# Laboratoire3_ClavierI2C.net
KiCad netlist of a schematic drawn in Altium Designer
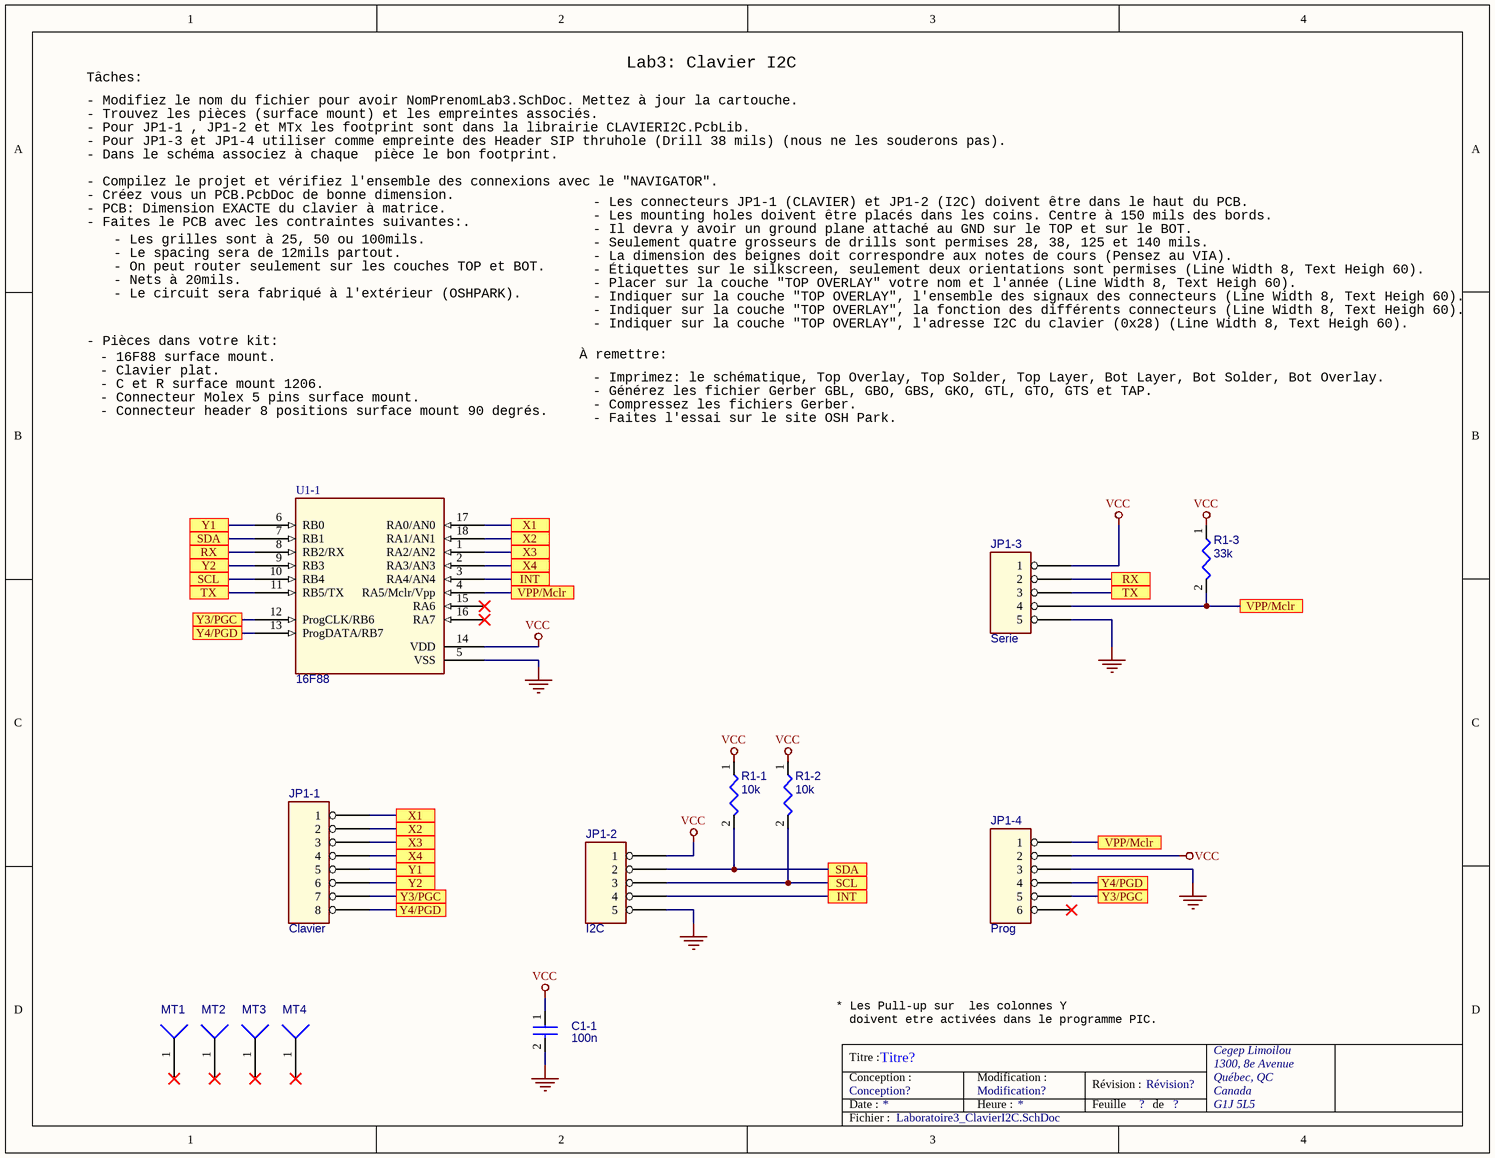
[diagram p0: Laboratoire3_ClavierI2C.SchDoc]

(export (version "E")
  (design (tool "Eeschema 10.0.6"))
  (components
    (comp (ref "C1-1") (value "100n") (libsource (lib "*") (part "CAP NP")))
    (comp (ref "JP1-1") (value "Clavier") (libsource (lib "*") (part "HEADER 8")))
    (comp (ref "JP1-2") (value "I2C") (libsource (lib "*") (part "HEADER 5")))
    (comp (ref "JP1-3") (value "Serie") (libsource (lib "*") (part "HEADER 5")))
    (comp (ref "JP1-4") (value "Prog") (libsource (lib "*") (part "HEADER 6")))
    (comp (ref "MT1") (value "MT") (libsource (lib "*") (part "CONNECTOR COAX-F")))
    (comp (ref "MT2") (value "MT") (libsource (lib "*") (part "CONNECTOR COAX-F")))
    (comp (ref "MT3") (value "MT") (libsource (lib "*") (part "CONNECTOR COAX-F")))
    (comp (ref "MT4") (value "MT") (libsource (lib "*") (part "CONNECTOR COAX-F")))
    (comp (ref "R1-1") (value "10k") (libsource (lib "*") (part "R")))
    (comp (ref "R1-2") (value "10k") (libsource (lib "*") (part "R")))
    (comp (ref "R1-3") (value "33k") (libsource (lib "*") (part "R")))
    (comp (ref "U1-1") (value "16F88") (libsource (lib "CLAVIERI2C") (part "16F88")))
  )
  (nets
    (net (code "1") (name "/INT") (class "Default")
      (node (ref "JP1-2") (pin "4") (pinfunction "4_4") (pintype "passive"))
      (node (ref "U1-1") (pin "3") (pinfunction "RA4/AN4_3") (pintype "input"))
    )
    (net (code "2") (name "/RX") (class "Default")
      (node (ref "JP1-3") (pin "2") (pinfunction "2_2") (pintype "passive"))
      (node (ref "U1-1") (pin "8") (pinfunction "RB2/RX_8") (pintype "input"))
    )
    (net (code "3") (name "/SCL") (class "Default")
      (node (ref "JP1-2") (pin "3") (pinfunction "3_3") (pintype "passive"))
      (node (ref "R1-2") (pin "2") (pinfunction "2_2") (pintype "passive"))
      (node (ref "U1-1") (pin "10") (pinfunction "RB4_10") (pintype "input"))
    )
    (net (code "4") (name "/SDA") (class "Default")
      (node (ref "JP1-2") (pin "2") (pinfunction "2_2") (pintype "passive"))
      (node (ref "R1-1") (pin "2") (pinfunction "2_2") (pintype "passive"))
      (node (ref "U1-1") (pin "7") (pinfunction "RB1_7") (pintype "input"))
    )
    (net (code "5") (name "/TX") (class "Default")
      (node (ref "JP1-3") (pin "3") (pinfunction "3_3") (pintype "passive"))
      (node (ref "U1-1") (pin "11") (pinfunction "RB5/TX_11") (pintype "input"))
    )
    (net (code "6") (name "/VPP{slash}Mclr") (class "Default")
      (node (ref "JP1-3") (pin "4") (pinfunction "4_4") (pintype "passive"))
      (node (ref "JP1-4") (pin "1") (pinfunction "1_1") (pintype "passive"))
      (node (ref "R1-3") (pin "2") (pinfunction "2_2") (pintype "passive"))
      (node (ref "U1-1") (pin "4") (pinfunction "RA5/Mclr/Vpp_4") (pintype "input"))
    )
    (net (code "7") (name "/X1") (class "Default")
      (node (ref "JP1-1") (pin "1") (pinfunction "1_1") (pintype "passive"))
      (node (ref "U1-1") (pin "17") (pinfunction "RA0/AN0_17") (pintype "input"))
    )
    (net (code "8") (name "/X2") (class "Default")
      (node (ref "JP1-1") (pin "2") (pinfunction "2_2") (pintype "passive"))
      (node (ref "U1-1") (pin "18") (pinfunction "RA1/AN1_18") (pintype "input"))
    )
    (net (code "9") (name "/X3") (class "Default")
      (node (ref "JP1-1") (pin "3") (pinfunction "3_3") (pintype "passive"))
      (node (ref "U1-1") (pin "1") (pinfunction "RA2/AN2_1") (pintype "input"))
    )
    (net (code "10") (name "/X4") (class "Default")
      (node (ref "JP1-1") (pin "4") (pinfunction "4_4") (pintype "passive"))
      (node (ref "U1-1") (pin "2") (pinfunction "RA3/AN3_2") (pintype "input"))
    )
    (net (code "11") (name "/Y1") (class "Default")
      (node (ref "JP1-1") (pin "5") (pinfunction "5_5") (pintype "passive"))
      (node (ref "U1-1") (pin "6") (pinfunction "RB0_6") (pintype "input"))
    )
    (net (code "12") (name "/Y2") (class "Default")
      (node (ref "JP1-1") (pin "6") (pinfunction "6_6") (pintype "passive"))
      (node (ref "U1-1") (pin "9") (pinfunction "RB3_9") (pintype "input"))
    )
    (net (code "13") (name "/Y3{slash}PGC") (class "Default")
      (node (ref "JP1-1") (pin "7") (pinfunction "7_7") (pintype "passive"))
      (node (ref "JP1-4") (pin "5") (pinfunction "5_5") (pintype "passive"))
      (node (ref "U1-1") (pin "12") (pinfunction "ProgCLK/RB6_12") (pintype "input"))
    )
    (net (code "14") (name "/Y4{slash}PGD") (class "Default")
      (node (ref "JP1-1") (pin "8") (pinfunction "8_8") (pintype "passive"))
      (node (ref "JP1-4") (pin "4") (pinfunction "4_4") (pintype "passive"))
      (node (ref "U1-1") (pin "13") (pinfunction "ProgDATA/RB7_13") (pintype "input"))
    )
    (net (code "15") (name "GND") (class "Default")
      (node (ref "C1-1") (pin "2") (pinfunction "2_2") (pintype "passive"))
      (node (ref "JP1-2") (pin "5") (pinfunction "5_5") (pintype "passive"))
      (node (ref "JP1-3") (pin "5") (pinfunction "5_5") (pintype "passive"))
      (node (ref "JP1-4") (pin "3") (pinfunction "3_3") (pintype "passive"))
      (node (ref "U1-1") (pin "5") (pinfunction "VSS_5") (pintype "power_in"))
    )
    (net (code "16") (name "VCC") (class "Default")
      (node (ref "C1-1") (pin "1") (pinfunction "1_1") (pintype "passive"))
      (node (ref "JP1-2") (pin "1") (pinfunction "1_1") (pintype "passive"))
      (node (ref "JP1-3") (pin "1") (pinfunction "1_1") (pintype "passive"))
      (node (ref "JP1-4") (pin "2") (pinfunction "2_2") (pintype "passive"))
      (node (ref "R1-1") (pin "1") (pinfunction "1_1") (pintype "passive"))
      (node (ref "R1-2") (pin "1") (pinfunction "1_1") (pintype "passive"))
      (node (ref "R1-3") (pin "1") (pinfunction "1_1") (pintype "passive"))
      (node (ref "U1-1") (pin "14") (pinfunction "VDD_14") (pintype "power_in"))
    )
    (net (code "17") (name "unconnected-(JP1-4-Pad6)") (class "Default")
      (node (ref "JP1-4") (pin "6") (pinfunction "6_6") (pintype "passive+no_connect"))
    )
    (net (code "18") (name "unconnected-(MT1-A-Pad1)") (class "Default")
      (node (ref "MT1") (pin "1") (pinfunction "A_1") (pintype "passive+no_connect"))
    )
    (net (code "19") (name "unconnected-(MT2-A-Pad1)") (class "Default")
      (node (ref "MT2") (pin "1") (pinfunction "A_1") (pintype "passive+no_connect"))
    )
    (net (code "20") (name "unconnected-(MT3-A-Pad1)") (class "Default")
      (node (ref "MT3") (pin "1") (pinfunction "A_1") (pintype "passive+no_connect"))
    )
    (net (code "21") (name "unconnected-(MT4-A-Pad1)") (class "Default")
      (node (ref "MT4") (pin "1") (pinfunction "A_1") (pintype "passive+no_connect"))
    )
    (net (code "22") (name "unconnected-(U1-1-RA6-Pad15)") (class "Default")
      (node (ref "U1-1") (pin "15") (pinfunction "RA6_15") (pintype "input+no_connect"))
    )
    (net (code "23") (name "unconnected-(U1-1-RA7-Pad16)") (class "Default")
      (node (ref "U1-1") (pin "16") (pinfunction "RA7_16") (pintype "input+no_connect"))
    )
  )
)
